# sim800L.net
KiCad netlist of a schematic drawn in Altium Designer
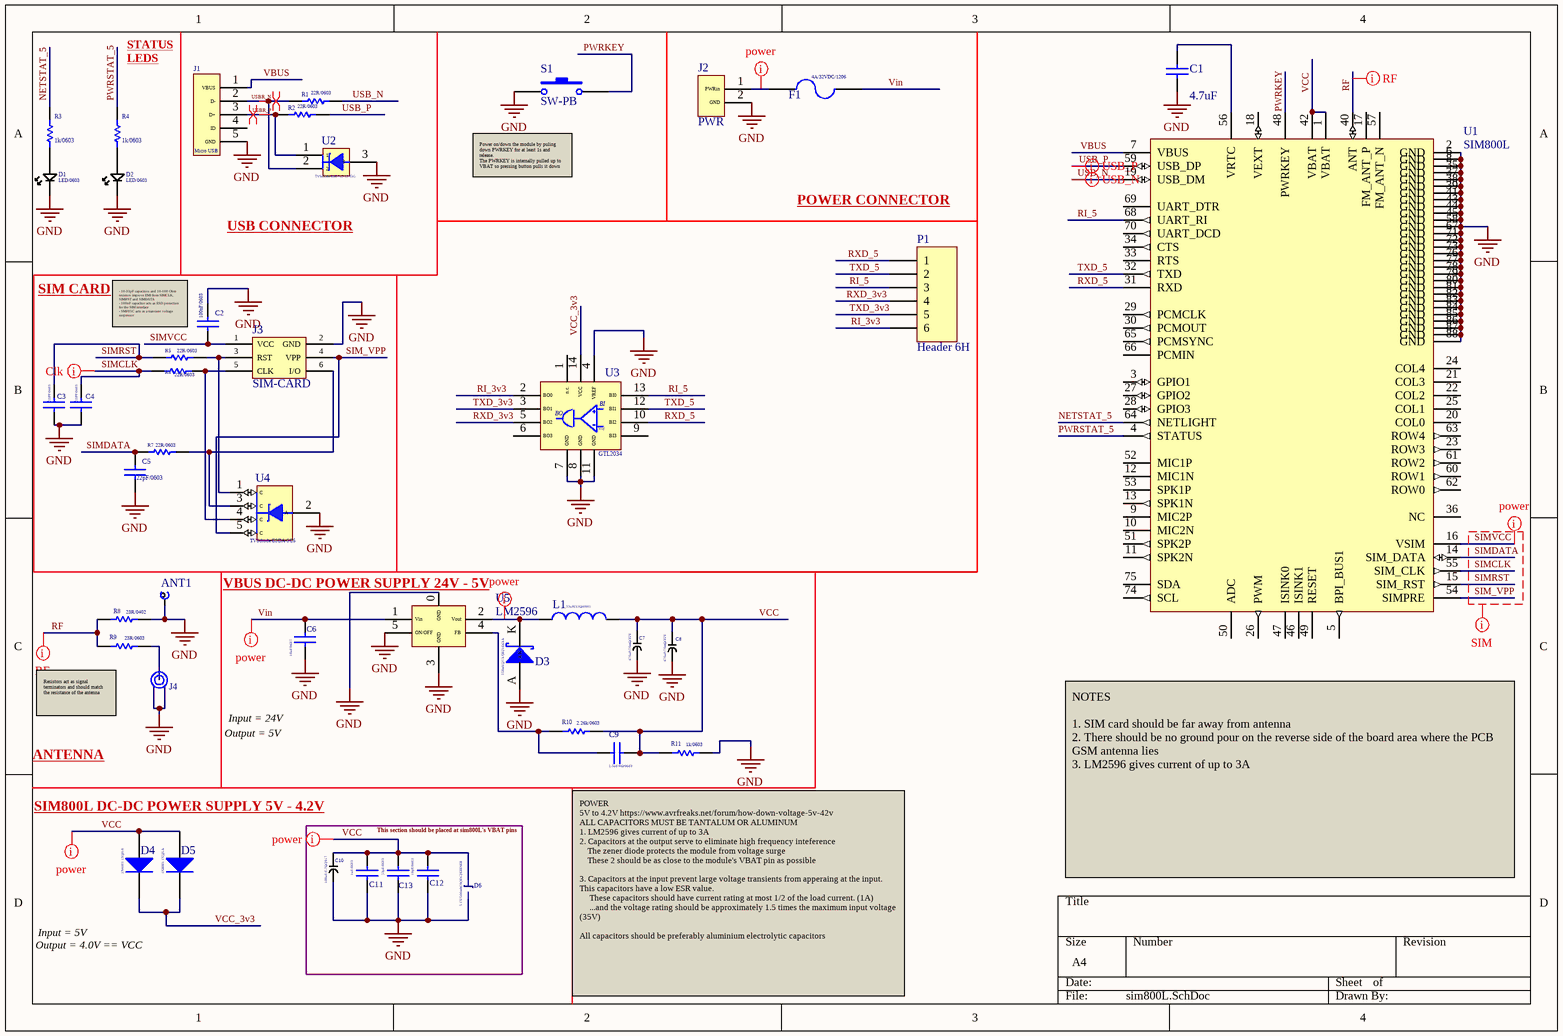
[diagram p0: sim800L.SchDoc]

(export (version "E")
  (design (tool "Eeschema 10.0.6"))
  (components
    (comp (ref "ANT1")
      (value "GSM-ANT")
      (footprint "GSM-ANTENNA")
      (libsource (lib "Pi_AddOn_Rev2") (part "GSM-ANT"))
    )
    (comp (ref "C1")
      (value "4.7uF")
      (footprint "0603")
      (description "Capacitor")
      (fields (field (name "Comment") "Cap") (field (name "PUBLISHER") "Altium Limited"))
      (libsource (lib "Miscellaneous Devices") (part "Cap"))
    )
    (comp (ref "C2")
      (value "100nF/0603")
      (footprint "0603")
      (description "Capacitor")
      (fields (field (name "Comment") "Cap") (field (name "PUBLISHER") "Altium Limited"))
      (libsource (lib "Miscellaneous Devices") (part "Cap"))
    )
    (comp (ref "C3")
      (value "33PF/0603")
      (footprint "0603")
      (description "Capacitor")
      (fields (field (name "Comment") "Cap") (field (name "PUBLISHER") "Altium Limited"))
      (libsource (lib "Miscellaneous Devices") (part "Cap"))
    )
    (comp (ref "C4")
      (value "33PF/0603")
      (footprint "0603")
      (description "Capacitor")
      (fields (field (name "Comment") "Cap") (field (name "PUBLISHER") "Altium Limited"))
      (libsource (lib "Miscellaneous Devices") (part "Cap"))
    )
    (comp (ref "C5")
      (value "22pF/0603")
      (footprint "0603")
      (description "Capacitor")
      (fields (field (name "Comment") "Cap") (field (name "PUBLISHER") "Altium Limited"))
      (libsource (lib "Miscellaneous Devices") (part "Cap"))
    )
    (comp (ref "C6")
      (value "10uF/0603")
      (footprint "0603")
      (description "Capacitor")
      (fields (field (name "Comment") "Cap") (field (name "PUBLISHER") "Altium Limited"))
      (libsource (lib "Miscellaneous Devices") (part "Cap"))
    )
    (comp (ref "C7")
      (value "470uF/70mΩ/35V")
      (footprint "Cap-Radial")
      (libsource (lib "sim800L_Schlib") (part "Cap-Pol"))
    )
    (comp (ref "C8")
      (value "470uF/70mΩ/35V")
      (footprint "Cap-Radial")
      (libsource (lib "sim800L_Schlib") (part "Cap-Pol"))
    )
    (comp (ref "C9")
      (value "1.5nF/0Ω/0603")
      (footprint "0603")
      (description "Capacitor")
      (fields (field (name "Comment") "Cap") (field (name "PUBLISHER") "Altium Limited"))
      (libsource (lib "Miscellaneous Devices") (part "Cap"))
    )
    (comp (ref "C10")
      (value "100uF/0.7Ω/2917")
      (footprint "2917-pol")
      (libsource (lib "sim800L_Schlib") (part "Cap-Pol"))
    )
    (comp (ref "C11")
      (value "1uF/0603")
      (footprint "0603")
      (description "Capacitor")
      (fields (field (name "PUBLISHER") "Altium Limited"))
      (libsource (lib "Miscellaneous Devices") (part "Cap"))
    )
    (comp (ref "C12")
      (value "10pF/0603")
      (footprint "0603")
      (description "Capacitor")
      (fields (field (name "PUBLISHER") "Altium Limited"))
      (libsource (lib "Miscellaneous Devices") (part "Cap"))
    )
    (comp (ref "C13")
      (value "33pF/0603")
      (footprint "0603")
      (description "Capacitor")
      (fields (field (name "PUBLISHER") "Altium Limited"))
      (libsource (lib "Miscellaneous Devices") (part "Cap"))
    )
    (comp (ref "D1")
      (value "LED/0603")
      (footprint "0603-LED- POL")
      (libsource (lib "Pi_AddOn_Rev2") (part "LED-SMD"))
    )
    (comp (ref "D2")
      (value "LED/0603")
      (footprint "0603-LED- POL")
      (libsource (lib "Pi_AddOn_Rev2") (part "LED-SMD"))
    )
    (comp (ref "D3")
      (value "550mV@7A/D02144AA")
      (footprint "DO-214AA - Power Diode")
      (fields (field (name "Comment") "Schottky Diode"))
      (libsource (lib "sim800L_Schlib") (part "Schottky Diode"))
    )
    (comp (ref "D4")
      (value "1N4001 1V@1A")
      (footprint "D0-214-AC")
      (description "1 Amp General Purpose Rectifier")
      (fields (field (name "PUBLISHER") "Altium Limited"))
      (libsource (lib "Miscellaneous Devices") (part "Diode 1N4001"))
    )
    (comp (ref "D5")
      (value "1N4001 1V@1A")
      (footprint "D0-214-AC")
      (description "1 Amp General Purpose Rectifier")
      (fields (field (name "PUBLISHER") "Altium Limited"))
      (libsource (lib "Miscellaneous Devices") (part "Diode 1N4001"))
    )
    (comp (ref "D6")
      (value "5.1V/500mW/SOD128ZENER")
      (footprint "SOD128-DIODE")
      (description "Zener Diode")
      (libsource (lib "Pi_AddOn_Rev2") (part "ZENER-DIODE"))
    )
    (comp (ref "F1")
      (value "4A/32VDC/1206")
      (footprint "fuse")
      (description "Fuse")
      (fields (field (name "PUBLISHER") "Altium Limited"))
      (libsource (lib "Miscellaneous Devices") (part "Fuse 2"))
    )
    (comp (ref "J1")
      (value "Micro USB")
      (footprint "micro_usb")
      (libsource (lib "sim800L_Schlib") (part "USB - micro B"))
    )
    (comp (ref "J2")
      (value "PWR")
      (footprint "SCREW TERMINAL 1X2")
      (libsource (lib "sim800L_Schlib") (part "Header 2"))
    )
    (comp (ref "J3")
      (value "SIM-CARD")
      (footprint "micro_sim")
      (description "6-PIN SIM HOLDER")
      (libsource (lib "sim800L_Schlib") (part "XNT-0121AAAA07A"))
    )
    (comp (ref "J4")
      (value "U.FL SMT coaxial connector")
      (footprint "U.FL_SMT_CON")
      (libsource (lib "Pi_AddOn_Rev2") (part "U.FL SMT coaxial connector"))
    )
    (comp (ref "L1")
      (value "33uH/33Ω/0805")
      (footprint "0805")
      (description "Inductor")
      (fields (field (name "PUBLISHER") "Altium Limited"))
      (libsource (lib "Miscellaneous Devices") (part "Inductor"))
    )
    (comp (ref "P1")
      (value "Header 6H")
      (footprint "HDR1X6")
      (description "Header, 6-Pin, Right Angle")
      (fields (field (name "PUBLISHER") "Altium Limited"))
      (libsource (lib "Miscellaneous Connectors") (part "Header 6H"))
    )
    (comp (ref "R1")
      (value "22R/0603")
      (footprint "0603")
      (description "Resistor")
      (fields (field (name "Comment") "0603") (field (name "PUBLISHER") "Altium Limited"))
      (libsource (lib "Miscellaneous Devices") (part "Res1"))
    )
    (comp (ref "R2")
      (value "22R/0603")
      (footprint "0603")
      (description "Resistor")
      (fields (field (name "Comment") "0603") (field (name "PUBLISHER") "Altium Limited"))
      (libsource (lib "Miscellaneous Devices") (part "Res1"))
    )
    (comp (ref "R3")
      (value "1k/0603")
      (footprint "0603")
      (description "Resistor")
      (fields (field (name "Comment") "Res1") (field (name "PUBLISHER") "Altium Limited"))
      (libsource (lib "Miscellaneous Devices") (part "Res1"))
    )
    (comp (ref "R4")
      (value "1k/0603")
      (footprint "0603")
      (description "Resistor")
      (fields (field (name "Comment") "Res1") (field (name "PUBLISHER") "Altium Limited"))
      (libsource (lib "Miscellaneous Devices") (part "Res1"))
    )
    (comp (ref "R5")
      (value "22R/0603")
      (footprint "0603")
      (description "Resistor")
      (fields (field (name "Comment") "Res1") (field (name "PUBLISHER") "Altium Limited"))
      (libsource (lib "Miscellaneous Devices") (part "Res1"))
    )
    (comp (ref "R6")
      (value "22R/0603")
      (footprint "0603")
      (description "Resistor")
      (fields (field (name "Comment") "Res1") (field (name "PUBLISHER") "Altium Limited"))
      (libsource (lib "Miscellaneous Devices") (part "Res1"))
    )
    (comp (ref "R7")
      (value "22R/0603")
      (footprint "0603")
      (description "Resistor")
      (fields (field (name "Comment") "Res1") (field (name "PUBLISHER") "Altium Limited"))
      (libsource (lib "Miscellaneous Devices") (part "Res1"))
    )
    (comp (ref "R8")
      (value "23R/0402")
      (footprint "0603")
      (description "Resistor")
      (fields (field (name "Comment") "Res1") (field (name "PUBLISHER") "Altium Limited"))
      (libsource (lib "Miscellaneous Devices") (part "Res1"))
    )
    (comp (ref "R9")
      (value "23R/0603")
      (footprint "0603")
      (description "Resistor")
      (fields (field (name "Comment") "Res1") (field (name "PUBLISHER") "Altium Limited"))
      (libsource (lib "Miscellaneous Devices") (part "Res1"))
    )
    (comp (ref "R10")
      (value "2.26k/0603")
      (footprint "0603")
      (description "Resistor")
      (fields (field (name "Comment") "Res1") (field (name "PUBLISHER") "Altium Limited"))
      (libsource (lib "Miscellaneous Devices") (part "Res1"))
    )
    (comp (ref "R11")
      (value "1k/0603")
      (footprint "0603")
      (description "Resistor")
      (fields (field (name "Comment") "Res1") (field (name "PUBLISHER") "Altium Limited"))
      (libsource (lib "Miscellaneous Devices") (part "Res1"))
    )
    (comp (ref "S1")
      (value "SW-PB")
      (footprint "SWITCH_smd_smt_2Lead")
      (description "Switch")
      (fields (field (name "PUBLISHER") "Altium Limited"))
      (libsource (lib "Miscellaneous Devices") (part "SW-PB"))
    )
    (comp (ref "U1")
      (value "SIM800L")
      (footprint "SIM800L-FOOTPRINT")
      (libsource (lib "sim800L_Schlib") (part "SIM800L"))
    )
    (comp (ref "U2")
      (value "TVSdiode-ESD7L5.0DT5G")
      (footprint "SOT-723")
      (libsource (lib "sim800L_Schlib") (part "SPS3222"))
    )
    (comp (ref "U3")
      (value "GTL2034")
      (footprint "TSSOP14")
      (libsource (lib "sim800L_Schlib") (part "GTL2034"))
    )
    (comp (ref "U4")
      (value "TVSdiode-ESDA-SC5")
      (footprint "SOT23-5PIN")
      (libsource (lib "sim800L_Schlib") (part "SMS05T1"))
    )
    (comp (ref "U5") (value "LM2596") (libsource (lib "sim800L_Schlib") (part "LM2596")))
  )
  (nets
    (net (code "1") (name "/NETSTAT_5") (class "Default")
      (node (ref "R3") (pin "2") (pinfunction "2_2") (pintype "passive"))
      (node (ref "U1") (pin "64") (pinfunction "NETLIGHT_64") (pintype "output"))
    )
    (net (code "2") (name "/PWRKEY") (class "Default")
      (node (ref "S1") (pin "2") (pinfunction "2_2") (pintype "passive"))
      (node (ref "U1") (pin "48") (pinfunction "PWRKEY_48") (pintype "passive"))
    )
    (net (code "3") (name "/PWRSTAT_5") (class "Default")
      (node (ref "R4") (pin "2") (pinfunction "2_2") (pintype "passive"))
      (node (ref "U1") (pin "4") (pinfunction "STATUS_4") (pintype "output"))
    )
    (net (code "4") (name "/RF") (class "Default")
      (node (ref "R8") (pin "1") (pinfunction "1_1") (pintype "passive"))
      (node (ref "R9") (pin "1") (pinfunction "1_1") (pintype "passive"))
      (node (ref "U1") (pin "40") (pinfunction "ANT_40") (pintype "bidirectional"))
    )
    (net (code "5") (name "/RI_3v3") (class "Default")
      (node (ref "P1") (pin "6") (pinfunction "6_6") (pintype "passive"))
      (node (ref "U3") (pin "2") (pinfunction "BO0_2") (pintype "passive"))
    )
    (net (code "6") (name "/RI_5") (class "Default")
      (node (ref "P1") (pin "3") (pinfunction "3_3") (pintype "passive"))
      (node (ref "U1") (pin "68") (pinfunction "UART_RI_68") (pintype "output"))
      (node (ref "U3") (pin "13") (pinfunction "BI0_13") (pintype "passive"))
    )
    (net (code "7") (name "/RXD_3v3") (class "Default")
      (node (ref "P1") (pin "4") (pinfunction "4_4") (pintype "passive"))
      (node (ref "U3") (pin "5") (pinfunction "BO2_5") (pintype "passive"))
    )
    (net (code "8") (name "/RXD_5") (class "Default")
      (node (ref "P1") (pin "1") (pinfunction "1_1") (pintype "passive"))
      (node (ref "U1") (pin "31") (pinfunction "RXD_31") (pintype "passive"))
      (node (ref "U3") (pin "10") (pinfunction "BI2_10") (pintype "passive"))
    )
    (net (code "9") (name "/SIMCLK") (class "Default")
      (node (ref "C4") (pin "2") (pinfunction "2_2") (pintype "passive"))
      (node (ref "R6") (pin "1") (pinfunction "1_1") (pintype "passive"))
      (node (ref "U1") (pin "55") (pinfunction "SIM_CLK_55") (pintype "output"))
    )
    (net (code "10") (name "/SIMDATA") (class "Default")
      (node (ref "C5") (pin "2") (pinfunction "2_2") (pintype "passive"))
      (node (ref "R7") (pin "1") (pinfunction "1_1") (pintype "passive"))
      (node (ref "U1") (pin "14") (pinfunction "SIM_DATA_14") (pintype "bidirectional"))
    )
    (net (code "11") (name "/SIMRST") (class "Default")
      (node (ref "C3") (pin "2") (pinfunction "2_2") (pintype "passive"))
      (node (ref "R5") (pin "1") (pinfunction "1_1") (pintype "passive"))
      (node (ref "U1") (pin "15") (pinfunction "SIM_RST_15") (pintype "output"))
    )
    (net (code "12") (name "/SIMVCC") (class "Default")
      (node (ref "C2") (pin "1") (pinfunction "1_1") (pintype "passive"))
      (node (ref "J3") (pin "1") (pinfunction "VCC_1") (pintype "passive"))
      (node (ref "U1") (pin "16") (pinfunction "VSIM_16") (pintype "passive"))
    )
    (net (code "13") (name "/SIM_VPP") (class "Default")
      (node (ref "J3") (pin "4") (pinfunction "VPP_4") (pintype "passive"))
      (node (ref "U1") (pin "54") (pinfunction "SIMPRE_54") (pintype "passive"))
      (node (ref "U4") (pin "5") (pinfunction "C_5") (pintype "bidirectional"))
    )
    (net (code "14") (name "/TXD_3v3") (class "Default")
      (node (ref "P1") (pin "5") (pinfunction "5_5") (pintype "passive"))
      (node (ref "U3") (pin "3") (pinfunction "BO1_3") (pintype "passive"))
    )
    (net (code "15") (name "/TXD_5") (class "Default")
      (node (ref "P1") (pin "2") (pinfunction "2_2") (pintype "passive"))
      (node (ref "U1") (pin "32") (pinfunction "TXD_32") (pintype "output"))
      (node (ref "U3") (pin "12") (pinfunction "BI1_12") (pintype "passive"))
    )
    (net (code "16") (name "/USBR_N") (class "Default")
      (node (ref "J1") (pin "2") (pinfunction "D-_2") (pintype "passive"))
      (node (ref "R1") (pin "1") (pinfunction "1_1") (pintype "passive"))
      (node (ref "U2") (pin "2") (pinfunction "2_2") (pintype "passive"))
    )
    (net (code "17") (name "/USBR_P") (class "Default")
      (node (ref "J1") (pin "3") (pinfunction "D+_3") (pintype "passive"))
      (node (ref "R2") (pin "1") (pinfunction "1_1") (pintype "passive"))
      (node (ref "U2") (pin "1") (pinfunction "1_1") (pintype "passive"))
    )
    (net (code "18") (name "/USB_N") (class "Default")
      (node (ref "R1") (pin "2") (pinfunction "2_2") (pintype "passive"))
      (node (ref "U1") (pin "19") (pinfunction "USB_DM_19") (pintype "bidirectional"))
    )
    (net (code "19") (name "/USB_P") (class "Default")
      (node (ref "R2") (pin "2") (pinfunction "2_2") (pintype "passive"))
      (node (ref "U1") (pin "59") (pinfunction "USB_DP_59") (pintype "bidirectional"))
    )
    (net (code "20") (name "/VBUS") (class "Default")
      (node (ref "J1") (pin "1") (pinfunction "VBUS_1") (pintype "passive"))
      (node (ref "U1") (pin "7") (pinfunction "VBUS_7") (pintype "passive"))
    )
    (net (code "21") (name "/VCC") (class "Default")
      (node (ref "C10") (pin "A") (pinfunction "A_A") (pintype "passive"))
      (node (ref "C11") (pin "2") (pinfunction "2_2") (pintype "passive"))
      (node (ref "C12") (pin "2") (pinfunction "2_2") (pintype "passive"))
      (node (ref "C13") (pin "2") (pinfunction "2_2") (pintype "passive"))
      (node (ref "C7") (pin "A") (pinfunction "A_A") (pintype "passive"))
      (node (ref "C8") (pin "A") (pinfunction "A_A") (pintype "passive"))
      (node (ref "C9") (pin "1") (pinfunction "1_1") (pintype "passive"))
      (node (ref "D4") (pin "1") (pinfunction "A_1") (pintype "passive"))
      (node (ref "D5") (pin "1") (pinfunction "A_1") (pintype "passive"))
      (node (ref "D6") (pin "K") (pinfunction "K_K") (pintype "passive"))
      (node (ref "L1") (pin "2") (pinfunction "2_2") (pintype "passive"))
      (node (ref "R10") (pin "2") (pinfunction "2_2") (pintype "passive"))
      (node (ref "R11") (pin "1") (pinfunction "1_1") (pintype "passive"))
      (node (ref "U1") (pin "1") (pinfunction "VBAT_1") (pintype "passive"))
      (node (ref "U1") (pin "42") (pinfunction "VBAT_42") (pintype "passive"))
    )
    (net (code "22") (name "/VCC_3v3") (class "Default")
      (node (ref "D4") (pin "2") (pinfunction "K_2") (pintype "passive"))
      (node (ref "D5") (pin "2") (pinfunction "K_2") (pintype "passive"))
      (node (ref "U3") (pin "14") (pinfunction "VCC_14") (pintype "passive"))
    )
    (net (code "23") (name "/Vin") (class "Default")
      (node (ref "C6") (pin "2") (pinfunction "2_2") (pintype "passive"))
      (node (ref "F1") (pin "2") (pinfunction "2_2") (pintype "passive"))
      (node (ref "U5") (pin "1") (pinfunction "Vin_1") (pintype "passive"))
    )
    (net (code "24") (name "GND") (class "Default")
      (node (ref "ANT1") (pin "1") (pinfunction "1_1") (pintype "passive"))
      (node (ref "C1") (pin "1") (pinfunction "1_1") (pintype "passive"))
      (node (ref "C10") (pin "K") (pinfunction "K_K") (pintype "passive"))
      (node (ref "C11") (pin "1") (pinfunction "1_1") (pintype "passive"))
      (node (ref "C12") (pin "1") (pinfunction "1_1") (pintype "passive"))
      (node (ref "C13") (pin "1") (pinfunction "1_1") (pintype "passive"))
      (node (ref "C2") (pin "2") (pinfunction "2_2") (pintype "passive"))
      (node (ref "C3") (pin "1") (pinfunction "1_1") (pintype "passive"))
      (node (ref "C4") (pin "1") (pinfunction "1_1") (pintype "passive"))
      (node (ref "C5") (pin "1") (pinfunction "1_1") (pintype "passive"))
      (node (ref "C6") (pin "1") (pinfunction "1_1") (pintype "passive"))
      (node (ref "C7") (pin "K") (pinfunction "K_K") (pintype "passive"))
      (node (ref "C8") (pin "K") (pinfunction "K_K") (pintype "passive"))
      (node (ref "D1") (pin "K") (pinfunction "K_K") (pintype "passive"))
      (node (ref "D2") (pin "K") (pinfunction "K_K") (pintype "passive"))
      (node (ref "D3") (pin "A") (pinfunction "A_A") (pintype "passive"))
      (node (ref "D6") (pin "A") (pinfunction "A_A") (pintype "passive"))
      (node (ref "J1") (pin "5") (pinfunction "GND_5") (pintype "passive"))
      (node (ref "J2") (pin "2") (pinfunction "GND_2") (pintype "passive"))
      (node (ref "J3") (pin "2") (pinfunction "GND_2") (pintype "passive"))
      (node (ref "J4") (pin "2") (pinfunction "2_2") (pintype "passive"))
      (node (ref "J4") (pin "3") (pinfunction "3_3") (pintype "passive"))
      (node (ref "R11") (pin "2") (pinfunction "2_2") (pintype "passive"))
      (node (ref "R8") (pin "2") (pinfunction "2_2") (pintype "passive"))
      (node (ref "S1") (pin "1") (pinfunction "1_1") (pintype "passive"))
      (node (ref "U1") (pin "2") (pinfunction "GND_2") (pintype "passive"))
      (node (ref "U1") (pin "35") (pinfunction "GND_35") (pintype "passive"))
      (node (ref "U1") (pin "37") (pinfunction "GND_37") (pintype "passive"))
      (node (ref "U1") (pin "38") (pinfunction "GND_38") (pintype "passive"))
      (node (ref "U1") (pin "39") (pinfunction "GND_39") (pintype "passive"))
      (node (ref "U1") (pin "41") (pinfunction "GND_41") (pintype "passive"))
      (node (ref "U1") (pin "43") (pinfunction "GND_43") (pintype "passive"))
      (node (ref "U1") (pin "44") (pinfunction "GND_44") (pintype "passive"))
      (node (ref "U1") (pin "45") (pinfunction "GND_45") (pintype "passive"))
      (node (ref "U1") (pin "58") (pinfunction "GND_58") (pintype "passive"))
      (node (ref "U1") (pin "6") (pinfunction "GND_6") (pintype "passive"))
      (node (ref "U1") (pin "67") (pinfunction "GND_67") (pintype "passive"))
      (node (ref "U1") (pin "71") (pinfunction "GND_71") (pintype "passive"))
      (node (ref "U1") (pin "72") (pinfunction "GND_72") (pintype "passive"))
      (node (ref "U1") (pin "73") (pinfunction "GND_73") (pintype "passive"))
      (node (ref "U1") (pin "76") (pinfunction "GND_76") (pintype "passive"))
      (node (ref "U1") (pin "77") (pinfunction "GND_77") (pintype "passive"))
      (node (ref "U1") (pin "78") (pinfunction "GND_78") (pintype "passive"))
      (node (ref "U1") (pin "79") (pinfunction "GND_79") (pintype "passive"))
      (node (ref "U1") (pin "8") (pinfunction "GND_8") (pintype "passive"))
      (node (ref "U1") (pin "80") (pinfunction "GND_80") (pintype "passive"))
      (node (ref "U1") (pin "81") (pinfunction "GND_81") (pintype "passive"))
      (node (ref "U1") (pin "82") (pinfunction "GND_82") (pintype "passive"))
      (node (ref "U1") (pin "83") (pinfunction "GND_83") (pintype "passive"))
      (node (ref "U1") (pin "84") (pinfunction "GND_84") (pintype "passive"))
      (node (ref "U1") (pin "85") (pinfunction "GND_85") (pintype "passive"))
      (node (ref "U1") (pin "86") (pinfunction "GND_86") (pintype "passive"))
      (node (ref "U1") (pin "87") (pinfunction "GND_87") (pintype "passive"))
      (node (ref "U1") (pin "88") (pinfunction "GND_88") (pintype "passive"))
      (node (ref "U2") (pin "3") (pinfunction "3_3") (pintype "passive"))
      (node (ref "U3") (pin "11") (pinfunction "GND_11") (pintype "passive"))
      (node (ref "U3") (pin "4") (pinfunction "VREF_4") (pintype "passive"))
      (node (ref "U3") (pin "7") (pinfunction "GND_7") (pintype "passive"))
      (node (ref "U3") (pin "8") (pinfunction "GND_8") (pintype "passive"))
      (node (ref "U4") (pin "2") (pinfunction "A_2") (pintype "passive"))
      (node (ref "U5") (pin "0") (pinfunction "GND_0") (pintype "passive"))
      (node (ref "U5") (pin "3") (pinfunction "GND_3") (pintype "passive"))
      (node (ref "U5") (pin "5") (pinfunction "ON/OFF_5") (pintype "passive"))
    )
    (net (code "25") (name "Net-(D1-PadA)") (class "Default")
      (node (ref "D1") (pin "A") (pinfunction "A_A") (pintype "passive"))
      (node (ref "R3") (pin "1") (pinfunction "1_1") (pintype "passive"))
    )
    (net (code "26") (name "Net-(D2-PadA)") (class "Default")
      (node (ref "D2") (pin "A") (pinfunction "A_A") (pintype "passive"))
      (node (ref "R4") (pin "1") (pinfunction "1_1") (pintype "passive"))
    )
    (net (code "27") (name "Net-(J2-PWRin)") (class "Default")
      (node (ref "F1") (pin "1") (pinfunction "1_1") (pintype "passive"))
      (node (ref "J2") (pin "1") (pinfunction "PWRin_1") (pintype "power_in"))
    )
    (net (code "28") (name "Net-(J3-CLK)") (class "Default")
      (node (ref "J3") (pin "5") (pinfunction "CLK_5") (pintype "passive"))
      (node (ref "R6") (pin "2") (pinfunction "2_2") (pintype "passive"))
      (node (ref "U4") (pin "4") (pinfunction "C_4") (pintype "bidirectional"))
    )
    (net (code "29") (name "Net-(J3-I{slash}O)") (class "Default")
      (node (ref "J3") (pin "6") (pinfunction "I/O_6") (pintype "passive"))
      (node (ref "R7") (pin "2") (pinfunction "2_2") (pintype "passive"))
      (node (ref "U4") (pin "3") (pinfunction "C_3") (pintype "bidirectional"))
    )
    (net (code "30") (name "Net-(J3-RST)") (class "Default")
      (node (ref "J3") (pin "3") (pinfunction "RST_3") (pintype "passive"))
      (node (ref "R5") (pin "2") (pinfunction "2_2") (pintype "passive"))
      (node (ref "U4") (pin "1") (pinfunction "C_1") (pintype "bidirectional"))
    )
    (net (code "31") (name "Net-(J4-Pad1)") (class "Default")
      (node (ref "J4") (pin "1") (pinfunction "1_1") (pintype "passive"))
      (node (ref "R9") (pin "2") (pinfunction "2_2") (pintype "passive"))
    )
    (net (code "32") (name "Net-(U1-VRTC)") (class "Default")
      (node (ref "C1") (pin "2") (pinfunction "2_2") (pintype "passive"))
      (node (ref "U1") (pin "56") (pinfunction "VRTC_56") (pintype "passive"))
    )
    (net (code "33") (name "Net-(U5-FB)") (class "Default")
      (node (ref "C9") (pin "2") (pinfunction "2_2") (pintype "passive"))
      (node (ref "R10") (pin "1") (pinfunction "1_1") (pintype "passive"))
      (node (ref "U5") (pin "4") (pinfunction "FB_4") (pintype "passive"))
    )
    (net (code "34") (name "Net-(U5-Vout)") (class "Default")
      (node (ref "D3") (pin "K") (pinfunction "K_K") (pintype "passive"))
      (node (ref "L1") (pin "1") (pinfunction "1_1") (pintype "passive"))
      (node (ref "U5") (pin "2") (pinfunction "Vout_2") (pintype "passive"))
    )
    (net (code "35") (name "unconnected-(J1-ID-Pad4)") (class "Default")
      (node (ref "J1") (pin "4") (pinfunction "ID_4") (pintype "passive"))
    )
    (net (code "36") (name "unconnected-(U1-ADC-Pad50)") (class "Default")
      (node (ref "U1") (pin "50") (pinfunction "ADC_50") (pintype "passive"))
    )
    (net (code "37") (name "unconnected-(U1-BPI_BUS1-Pad5)") (class "Default")
      (node (ref "U1") (pin "5") (pinfunction "BPI_BUS1_5") (pintype "output"))
    )
    (net (code "38") (name "unconnected-(U1-COL0-Pad20)") (class "Default")
      (node (ref "U1") (pin "20") (pinfunction "COL0_20") (pintype "passive"))
    )
    (net (code "39") (name "unconnected-(U1-COL1-Pad25)") (class "Default")
      (node (ref "U1") (pin "25") (pinfunction "COL1_25") (pintype "passive"))
    )
    (net (code "40") (name "unconnected-(U1-COL2-Pad22)") (class "Default")
      (node (ref "U1") (pin "22") (pinfunction "COL2_22") (pintype "passive"))
    )
    (net (code "41") (name "unconnected-(U1-COL3-Pad21)") (class "Default")
      (node (ref "U1") (pin "21") (pinfunction "COL3_21") (pintype "passive"))
    )
    (net (code "42") (name "unconnected-(U1-COL4-Pad24)") (class "Default")
      (node (ref "U1") (pin "24") (pinfunction "COL4_24") (pintype "passive"))
    )
    (net (code "43") (name "unconnected-(U1-CTS-Pad34)") (class "Default")
      (node (ref "U1") (pin "34") (pinfunction "CTS_34") (pintype "output"))
    )
    (net (code "44") (name "unconnected-(U1-FM_ANT_N-Pad57)") (class "Default")
      (node (ref "U1") (pin "57") (pinfunction "FM_ANT_N_57") (pintype "passive"))
    )
    (net (code "45") (name "unconnected-(U1-FM_ANT_P-Pad17)") (class "Default")
      (node (ref "U1") (pin "17") (pinfunction "FM_ANT_P_17") (pintype "passive"))
    )
    (net (code "46") (name "unconnected-(U1-GPIO1-Pad3)") (class "Default")
      (node (ref "U1") (pin "3") (pinfunction "GPIO1_3") (pintype "bidirectional"))
    )
    (net (code "47") (name "unconnected-(U1-GPIO2-Pad27)") (class "Default")
      (node (ref "U1") (pin "27") (pinfunction "GPIO2_27") (pintype "bidirectional"))
    )
    (net (code "48") (name "unconnected-(U1-GPIO3-Pad28)") (class "Default")
      (node (ref "U1") (pin "28") (pinfunction "GPIO3_28") (pintype "bidirectional"))
    )
    (net (code "49") (name "unconnected-(U1-ISINK0-Pad47)") (class "Default")
      (node (ref "U1") (pin "47") (pinfunction "ISINK0_47") (pintype "passive"))
    )
    (net (code "50") (name "unconnected-(U1-ISINK1-Pad46)") (class "Default")
      (node (ref "U1") (pin "46") (pinfunction "ISINK1_46") (pintype "passive"))
    )
    (net (code "51") (name "unconnected-(U1-MIC1N-Pad12)") (class "Default")
      (node (ref "U1") (pin "12") (pinfunction "MIC1N_12") (pintype "passive"))
    )
    (net (code "52") (name "unconnected-(U1-MIC1P-Pad52)") (class "Default")
      (node (ref "U1") (pin "52") (pinfunction "MIC1P_52") (pintype "passive"))
    )
    (net (code "53") (name "unconnected-(U1-MIC2N-Pad10)") (class "Default")
      (node (ref "U1") (pin "10") (pinfunction "MIC2N_10") (pintype "passive"))
    )
    (net (code "54") (name "unconnected-(U1-MIC2P-Pad9)") (class "Default")
      (node (ref "U1") (pin "9") (pinfunction "MIC2P_9") (pintype "passive"))
    )
    (net (code "55") (name "unconnected-(U1-NC-Pad36)") (class "Default")
      (node (ref "U1") (pin "36") (pinfunction "NC_36") (pintype "passive"))
    )
    (net (code "56") (name "unconnected-(U1-PCMCLK-Pad29)") (class "Default")
      (node (ref "U1") (pin "29") (pinfunction "PCMCLK_29") (pintype "output"))
    )
    (net (code "57") (name "unconnected-(U1-PCMIN-Pad66)") (class "Default")
      (node (ref "U1") (pin "66") (pinfunction "PCMIN_66") (pintype "passive"))
    )
    (net (code "58") (name "unconnected-(U1-PCMOUT-Pad30)") (class "Default")
      (node (ref "U1") (pin "30") (pinfunction "PCMOUT_30") (pintype "output"))
    )
    (net (code "59") (name "unconnected-(U1-PCMSYNC-Pad65)") (class "Default")
      (node (ref "U1") (pin "65") (pinfunction "PCMSYNC_65") (pintype "output"))
    )
    (net (code "60") (name "unconnected-(U1-PWM-Pad26)") (class "Default")
      (node (ref "U1") (pin "26") (pinfunction "PWM_26") (pintype "output"))
    )
    (net (code "61") (name "unconnected-(U1-RESET-Pad49)") (class "Default")
      (node (ref "U1") (pin "49") (pinfunction "RESET_49") (pintype "passive"))
    )
    (net (code "62") (name "unconnected-(U1-ROW0-Pad62)") (class "Default")
      (node (ref "U1") (pin "62") (pinfunction "ROW0_62") (pintype "output"))
    )
    (net (code "63") (name "unconnected-(U1-ROW1-Pad60)") (class "Default")
      (node (ref "U1") (pin "60") (pinfunction "ROW1_60") (pintype "output"))
    )
    (net (code "64") (name "unconnected-(U1-ROW2-Pad61)") (class "Default")
      (node (ref "U1") (pin "61") (pinfunction "ROW2_61") (pintype "output"))
    )
    (net (code "65") (name "unconnected-(U1-ROW3-Pad23)") (class "Default")
      (node (ref "U1") (pin "23") (pinfunction "ROW3_23") (pintype "output"))
    )
    (net (code "66") (name "unconnected-(U1-ROW4-Pad63)") (class "Default")
      (node (ref "U1") (pin "63") (pinfunction "ROW4_63") (pintype "output"))
    )
    (net (code "67") (name "unconnected-(U1-RTS-Pad33)") (class "Default")
      (node (ref "U1") (pin "33") (pinfunction "RTS_33") (pintype "passive"))
    )
    (net (code "68") (name "unconnected-(U1-SCL-Pad74)") (class "Default")
      (node (ref "U1") (pin "74") (pinfunction "SCL_74") (pintype "output"))
    )
    (net (code "69") (name "unconnected-(U1-SDA-Pad75)") (class "Default")
      (node (ref "U1") (pin "75") (pinfunction "SDA_75") (pintype "passive"))
    )
    (net (code "70") (name "unconnected-(U1-SPK1N-Pad13)") (class "Default")
      (node (ref "U1") (pin "13") (pinfunction "SPK1N_13") (pintype "output"))
    )
    (net (code "71") (name "unconnected-(U1-SPK1P-Pad53)") (class "Default")
      (node (ref "U1") (pin "53") (pinfunction "SPK1P_53") (pintype "passive"))
    )
    (net (code "72") (name "unconnected-(U1-SPK2N-Pad11)") (class "Default")
      (node (ref "U1") (pin "11") (pinfunction "SPK2N_11") (pintype "output"))
    )
    (net (code "73") (name "unconnected-(U1-SPK2P-Pad51)") (class "Default")
      (node (ref "U1") (pin "51") (pinfunction "SPK2P_51") (pintype "output"))
    )
    (net (code "74") (name "unconnected-(U1-UART_DCD-Pad70)") (class "Default")
      (node (ref "U1") (pin "70") (pinfunction "UART_DCD_70") (pintype "output"))
    )
    (net (code "75") (name "unconnected-(U1-UART_DTR-Pad69)") (class "Default")
      (node (ref "U1") (pin "69") (pinfunction "UART_DTR_69") (pintype "passive"))
    )
    (net (code "76") (name "unconnected-(U1-VEXT-Pad18)") (class "Default")
      (node (ref "U1") (pin "18") (pinfunction "VEXT_18") (pintype "bidirectional"))
    )
    (net (code "77") (name "unconnected-(U3-BI3-Pad9)") (class "Default")
      (node (ref "U3") (pin "9") (pinfunction "BI3_9") (pintype "passive"))
    )
    (net (code "78") (name "unconnected-(U3-BO3-Pad6)") (class "Default")
      (node (ref "U3") (pin "6") (pinfunction "BO3_6") (pintype "passive"))
    )
    (net (code "79") (name "unconnected-(U3-n.c.-Pad1)") (class "Default")
      (node (ref "U3") (pin "1") (pinfunction "n.c._1") (pintype "passive"))
    )
  )
)
